# 464HardwareProject.net
KiCad netlist of a schematic drawn in Altium Designer
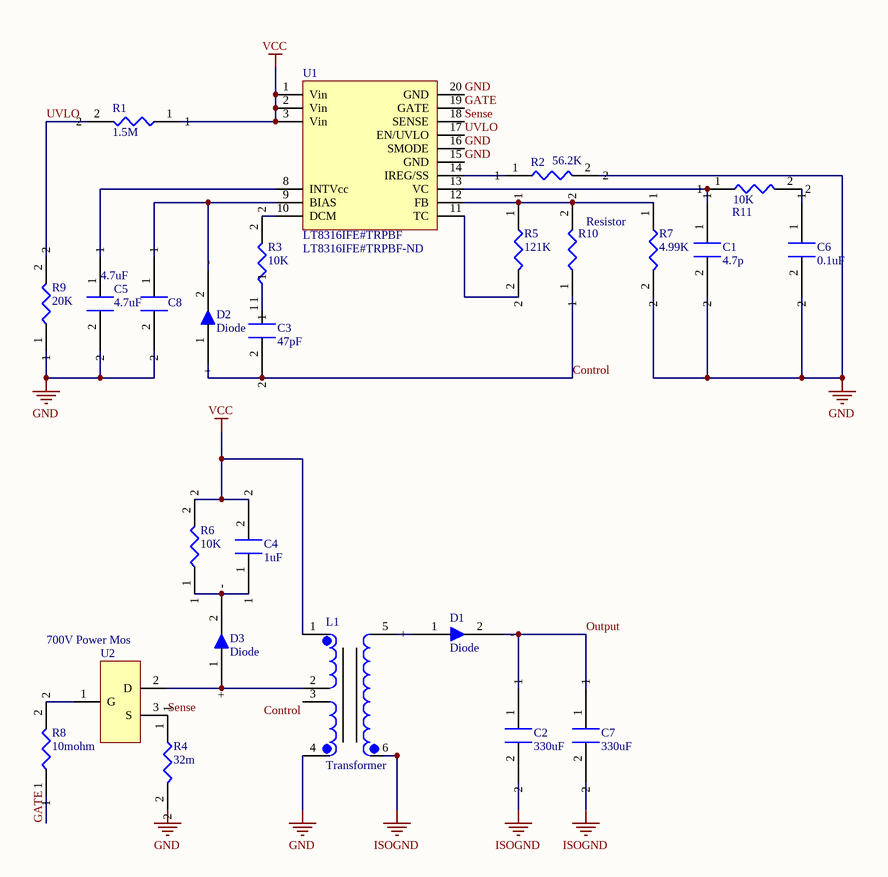
[diagram p0: 464HardwareProject.SchDoc]

(export (version "E")
  (design (tool "Eeschema 10.0.6"))
  (components
    (comp (ref "C1")
      (value "4.7p")
      (footprint "C1 C0402 47pF")
      (libsource (lib "464HardwareProject") (part "Capacitor"))
    )
    (comp (ref "C2")
      (value "330uF")
      (footprint "C2 Output Cap 330uF 16V 13mohm")
      (libsource (lib "464HardwareProject") (part "Capacitor"))
    )
    (comp (ref "C3")
      (value "47pF")
      (footprint "C3 C0402 47pF 100V")
      (libsource (lib "464HardwareProject") (part "Capacitor"))
    )
    (comp (ref "C4")
      (value "1uF")
      (footprint "C6 C0402 1uF")
      (libsource (lib "464HardwareProject") (part "Capacitor"))
    )
    (comp (ref "C5")
      (value "4.7uF")
      (footprint "C6 C0402 1uF")
      (libsource (lib "464HardwareProject") (part "Capacitor"))
    )
    (comp (ref "C6")
      (value "0.1uF")
      (footprint "C6 C0402 1uF")
      (libsource (lib "464HardwareProject") (part "Capacitor"))
    )
    (comp (ref "C7")
      (value "330uF")
      (footprint "C2 Output Cap 330uF 16V 13mohm")
      (libsource (lib "464HardwareProject") (part "Capacitor"))
    )
    (comp (ref "C8")
      (value "4.7uF")
      (footprint "C4 C0402 4.7uF 16V")
      (libsource (lib "464HardwareProject") (part "Capacitor"))
    )
    (comp (ref "D1")
      (value "Diode")
      (footprint "D1 40A 860 mv TO220-2")
      (libsource (lib "464HardwareProject") (part "Diode"))
    )
    (comp (ref "D2")
      (value "Diode")
      (footprint "D2 1A 470mV SOD323-2")
      (libsource (lib "464HardwareProject") (part "Diode"))
    )
    (comp (ref "D3")
      (value "Diode")
      (footprint "D3 5A 1.15V DO-214AB")
      (libsource (lib "464HardwareProject") (part "Diode"))
    )
    (comp (ref "L1")
      (value "Transformer")
      (footprint "Transformer")
      (libsource (lib "464HardwareProject") (part "Transformer"))
    )
    (comp (ref "R1")
      (value "1.5M")
      (footprint "R1 R0402 1.5M 0.2W")
      (libsource (lib "464HardwareProject") (part "Resistor"))
    )
    (comp (ref "R2")
      (value "56.2K")
      (footprint "R2 R0402 56.2K")
      (libsource (lib "464HardwareProject") (part "Resistor"))
    )
    (comp (ref "R3")
      (value "10K")
      (footprint "R3 R0805 10K 1W wide-chip")
      (libsource (lib "464HardwareProject") (part "Resistor"))
    )
    (comp (ref "R4")
      (value "32m")
      (footprint "R4 R0603 32mohm sense")
      (libsource (lib "464HardwareProject") (part "Resistor"))
    )
    (comp (ref "R5")
      (value "121K")
      (footprint "R5 R0402 121K")
      (libsource (lib "464HardwareProject") (part "Resistor"))
    )
    (comp (ref "R6")
      (value "10K")
      (footprint "R11 R3540 10K 4W snubber")
      (libsource (lib "464HardwareProject") (part "Resistor"))
    )
    (comp (ref "R7")
      (value "4.99K")
      (footprint "R7 R0402 4.99K")
      (libsource (lib "464HardwareProject") (part "Resistor"))
    )
    (comp (ref "R8")
      (value "10mohm")
      (footprint "R10 R0402 10mohm gate")
      (libsource (lib "464HardwareProject") (part "Resistor"))
    )
    (comp (ref "R9")
      (value "20K")
      (footprint "R9 R0402 20K")
      (libsource (lib "464HardwareProject") (part "Resistor"))
    )
    (comp (ref "R10")
      (value "Resistor")
      (footprint "R6 R0402 44.2K 0.25W")
      (libsource (lib "464HardwareProject") (part "Resistor"))
    )
    (comp (ref "R11")
      (value "10K")
      (footprint "R8 R0402 10K")
      (libsource (lib "464HardwareProject") (part "Resistor"))
    )
    (comp (ref "U1")
      (value "LT8316IFE#TRPBF")
      (footprint "LT8316")
      (description "DC/DC Cntrlr Single-OUT 142kHz Automotive 16-Pin TSSOP EP T/R")
      (fields
        (field (name "MANUFACTURER") "Analog Devices")
        (field (name "SUPPLIER PART NUMBER 1") "LT8316IFE#TRPBF-ND")
      )
      (libsource (lib "464HardwareProject") (part "LT8316IFE#TRPBF"))
    )
    (comp (ref "U2")
      (value "700V Power Mos")
      (footprint "700V mos")
      (libsource (lib "464HardwareProject") (part "700V Power Mos"))
    )
  )
  (nets
    (net (code "1") (name "/Control") (class "Default")
      (node (ref "C3") (pin "2") (pinfunction "2_2") (pintype "passive"))
      (node (ref "D2") (pin "1") (pinfunction "+_1") (pintype "passive"))
      (node (ref "L1") (pin "3") (pinfunction "L3+_3") (pintype "passive"))
      (node (ref "R10") (pin "1") (pinfunction "1_1") (pintype "passive"))
    )
    (net (code "2") (name "/GATE") (class "Default")
      (node (ref "R8") (pin "1") (pinfunction "1_1") (pintype "passive"))
      (node (ref "U1") (pin "19") (pinfunction "GATE_19") (pintype "passive"))
    )
    (net (code "3") (name "/Output") (class "Default")
      (node (ref "C2") (pin "1") (pinfunction "1_1") (pintype "passive"))
      (node (ref "C7") (pin "1") (pinfunction "1_1") (pintype "passive"))
      (node (ref "D1") (pin "2") (pinfunction "-_2") (pintype "passive"))
    )
    (net (code "4") (name "/Sense") (class "Default")
      (node (ref "R4") (pin "1") (pinfunction "1_1") (pintype "passive"))
      (node (ref "U1") (pin "18") (pinfunction "SENSE_18") (pintype "passive"))
      (node (ref "U2") (pin "3") (pinfunction "S_3") (pintype "passive"))
    )
    (net (code "5") (name "/UVLO") (class "Default")
      (node (ref "R1") (pin "2") (pinfunction "2_2") (pintype "passive"))
      (node (ref "R9") (pin "2") (pinfunction "2_2") (pintype "passive"))
      (node (ref "U1") (pin "17") (pinfunction "EN/UVLO_17") (pintype "passive"))
    )
    (net (code "6") (name "GND") (class "Default")
      (node (ref "C1") (pin "2") (pinfunction "2_2") (pintype "passive"))
      (node (ref "C5") (pin "2") (pinfunction "2_2") (pintype "passive"))
      (node (ref "C6") (pin "2") (pinfunction "2_2") (pintype "passive"))
      (node (ref "C8") (pin "2") (pinfunction "2_2") (pintype "passive"))
      (node (ref "L1") (pin "4") (pinfunction "L3-_4") (pintype "passive"))
      (node (ref "R2") (pin "2") (pinfunction "2_2") (pintype "passive"))
      (node (ref "R4") (pin "2") (pinfunction "2_2") (pintype "passive"))
      (node (ref "R7") (pin "2") (pinfunction "2_2") (pintype "passive"))
      (node (ref "R9") (pin "1") (pinfunction "1_1") (pintype "passive"))
      (node (ref "U1") (pin "15") (pinfunction "GND_15") (pintype "passive"))
      (node (ref "U1") (pin "16") (pinfunction "SMODE_16") (pintype "passive"))
      (node (ref "U1") (pin "20") (pinfunction "GND_20") (pintype "passive"))
    )
    (net (code "7") (name "ISOGND") (class "Default")
      (node (ref "C2") (pin "2") (pinfunction "2_2") (pintype "passive"))
      (node (ref "C7") (pin "2") (pinfunction "2_2") (pintype "passive"))
      (node (ref "L1") (pin "6") (pinfunction "L2-_6") (pintype "passive"))
    )
    (net (code "8") (name "Net-(C3-Pad1)") (class "Default")
      (node (ref "C3") (pin "1") (pinfunction "1_1") (pintype "passive"))
      (node (ref "R3") (pin "1") (pinfunction "1_1") (pintype "passive"))
    )
    (net (code "9") (name "Net-(C6-Pad1)") (class "Default")
      (node (ref "C6") (pin "1") (pinfunction "1_1") (pintype "passive"))
      (node (ref "R11") (pin "2") (pinfunction "2_2") (pintype "passive"))
    )
    (net (code "10") (name "Net-(D1-+)") (class "Default")
      (node (ref "D1") (pin "1") (pinfunction "+_1") (pintype "passive"))
      (node (ref "L1") (pin "5") (pinfunction "L2+_5") (pintype "passive"))
    )
    (net (code "11") (name "Net-(D2--)") (class "Default")
      (node (ref "C8") (pin "1") (pinfunction "1_1") (pintype "passive"))
      (node (ref "D2") (pin "2") (pinfunction "-_2") (pintype "passive"))
      (node (ref "U1") (pin "9") (pinfunction "BIAS_9") (pintype "passive"))
    )
    (net (code "12") (name "Net-(D3-+)") (class "Default")
      (node (ref "D3") (pin "1") (pinfunction "+_1") (pintype "passive"))
      (node (ref "L1") (pin "2") (pinfunction "L1_-_2") (pintype "passive"))
      (node (ref "U2") (pin "2") (pinfunction "D_2") (pintype "passive"))
    )
    (net (code "13") (name "Net-(D3--)") (class "Default")
      (node (ref "C4") (pin "1") (pinfunction "1_1") (pintype "passive"))
      (node (ref "D3") (pin "2") (pinfunction "-_2") (pintype "passive"))
      (node (ref "R6") (pin "1") (pinfunction "1_1") (pintype "passive"))
    )
    (net (code "14") (name "Net-(U1-DCM)") (class "Default")
      (node (ref "R3") (pin "2") (pinfunction "2_2") (pintype "passive"))
      (node (ref "U1") (pin "10") (pinfunction "DCM_10") (pintype "passive"))
    )
    (net (code "15") (name "Net-(U1-FB)") (class "Default")
      (node (ref "R10") (pin "2") (pinfunction "2_2") (pintype "passive"))
      (node (ref "R5") (pin "1") (pinfunction "1_1") (pintype "passive"))
      (node (ref "R7") (pin "1") (pinfunction "1_1") (pintype "passive"))
      (node (ref "U1") (pin "12") (pinfunction "FB_12") (pintype "passive"))
    )
    (net (code "16") (name "Net-(U1-INTVcc)") (class "Default")
      (node (ref "C5") (pin "1") (pinfunction "1_1") (pintype "passive"))
      (node (ref "U1") (pin "8") (pinfunction "INTVcc_8") (pintype "passive"))
    )
    (net (code "17") (name "Net-(U1-IREG{slash}SS)") (class "Default")
      (node (ref "R2") (pin "1") (pinfunction "1_1") (pintype "passive"))
      (node (ref "U1") (pin "14") (pinfunction "IREG/SS_14") (pintype "passive"))
    )
    (net (code "18") (name "Net-(U1-TC)") (class "Default")
      (node (ref "R5") (pin "2") (pinfunction "2_2") (pintype "passive"))
      (node (ref "U1") (pin "11") (pinfunction "TC_11") (pintype "passive"))
    )
    (net (code "19") (name "Net-(U1-VC)") (class "Default")
      (node (ref "C1") (pin "1") (pinfunction "1_1") (pintype "passive"))
      (node (ref "R11") (pin "1") (pinfunction "1_1") (pintype "passive"))
      (node (ref "U1") (pin "13") (pinfunction "VC_13") (pintype "passive"))
    )
    (net (code "20") (name "Net-(U2-G)") (class "Default")
      (node (ref "R8") (pin "2") (pinfunction "2_2") (pintype "passive"))
      (node (ref "U2") (pin "1") (pinfunction "G_1") (pintype "passive"))
    )
    (net (code "21") (name "VCC") (class "Default")
      (node (ref "C4") (pin "2") (pinfunction "2_2") (pintype "passive"))
      (node (ref "L1") (pin "1") (pinfunction "L1_+_1") (pintype "passive"))
      (node (ref "R1") (pin "1") (pinfunction "1_1") (pintype "passive"))
      (node (ref "R6") (pin "2") (pinfunction "2_2") (pintype "passive"))
      (node (ref "U1") (pin "1") (pinfunction "Vin_1") (pintype "passive"))
      (node (ref "U1") (pin "2") (pinfunction "Vin_2") (pintype "passive"))
      (node (ref "U1") (pin "3") (pinfunction "Vin_3") (pintype "passive"))
    )
  )
)
